# Boost.net
KiCad netlist of a schematic drawn in Altium Designer
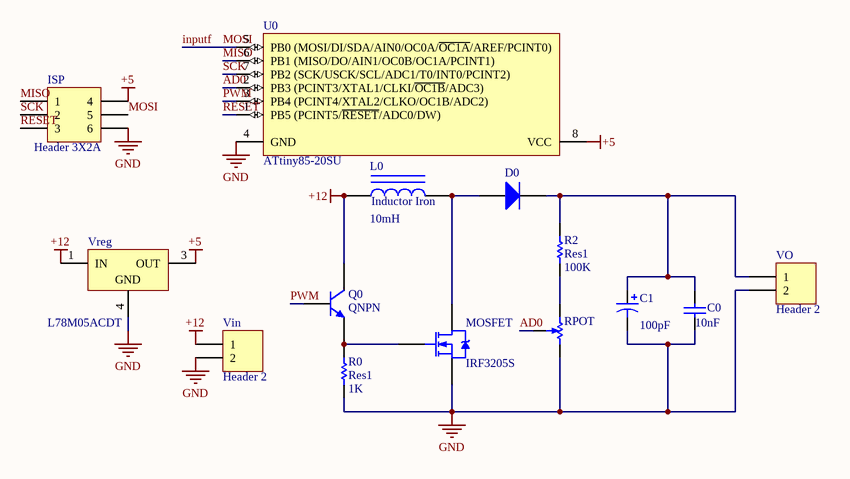
[diagram p0: Boost.SchDoc]

(export (version "E")
  (design (tool "Eeschema 10.0.6"))
  (components
    (comp (ref "C0")
      (value "10nF")
      (footprint "RB7.6-15")
      (description "Capacitor")
      (fields (field (name "Comment") "Cap") (field (name "PUBLISHER") "Altium Limited"))
      (libsource (lib "Miscellaneous Devices") (part "Cap"))
    )
    (comp (ref "C1")
      (value "100pF")
      (footprint "RAD-0.2")
      (description "Polarized Capacitor (Radial)")
      (fields (field (name "Comment") "Cap Pol1") (field (name "PUBLISHER") "Altium Limited"))
      (libsource (lib "Miscellaneous Devices") (part "Cap Pol1"))
    )
    (comp (ref "D0")
      (value "Diode BAS16")
      (footprint "SOT-23_L")
      (description "Silicon Switching Diode for High-Speed Switching")
      (fields (field (name "PUBLISHER") "Altium Limited"))
      (libsource (lib "Miscellaneous Devices") (part "Diode BAS16"))
    )
    (comp (ref "ISP")
      (value "Header 3X2A")
      (footprint "HDR2X3_CEN")
      (description "Header, 3-Pin, Dual row")
      (fields (field (name "PUBLISHER") "Altium Limited"))
      (libsource (lib "Miscellaneous Connectors") (part "Header 3X2A"))
    )
    (comp (ref "L0")
      (value "Inductor Iron")
      (footprint "AXIAL-0.9")
      (description "Magnetic-Core Inductor")
      (fields (field (name "ALTIUM_VALUE") "10mH") (field (name "PUBLISHER") "Altium Limited"))
      (libsource (lib "Miscellaneous Devices") (part "Inductor Iron"))
    )
    (comp (ref "MOSFET")
      (value "IRF3205S")
      (footprint "D2PAK_L")
      (description "HEXFET Power MOSFET")
      (fields (field (name "PUBLISHER") "Altium Limited"))
      (libsource (lib "IR Discrete MOSFET - Power") (part "IRF3205S"))
    )
    (comp (ref "Q0")
      (value "QNPN")
      (footprint "SOT-23B_L")
      (description "NPN Bipolar Transistor")
      (fields (field (name "PUBLISHER") "Altium Limited"))
      (libsource (lib "Miscellaneous Devices") (part "QNPN"))
    )
    (comp (ref "R0")
      (value "Res1")
      (footprint "j1-0603")
      (description "Resistor")
      (fields (field (name "ALTIUM_VALUE") "1K") (field (name "PUBLISHER") "Altium Limited"))
      (libsource (lib "Miscellaneous Devices") (part "Res1"))
    )
    (comp (ref "R2")
      (value "Res1")
      (footprint "j1-0603")
      (description "Resistor")
      (fields (field (name "ALTIUM_VALUE") "100K") (field (name "PUBLISHER") "Altium Limited"))
      (libsource (lib "Miscellaneous Devices") (part "Res1"))
    )
    (comp (ref "RPOT")
      (value "RPot SM")
      (footprint "POT4MM-2")
      (description "Square Trimming Potentiometer")
      (fields (field (name "PUBLISHER") "Altium Limited"))
      (libsource (lib "Miscellaneous Devices") (part "RPot SM"))
    )
    (comp (ref "U0")
      (value "ATtiny85-20SU")
      (footprint "8S2_L")
      (fields (field (name "PUBLISHER") "Altium Limited"))
      (libsource (lib "Atmel Microcontroller 8-Bit tinyAVR") (part "ATtiny85-20SU"))
    )
    (comp (ref "Vin")
      (value "Header 2")
      (footprint "HDR1X2")
      (description "Header, 2-Pin")
      (fields (field (name "PUBLISHER") "Altium Limited"))
      (libsource (lib "Miscellaneous Connectors") (part "Header 2"))
    )
    (comp (ref "VO")
      (value "Header 2")
      (footprint "HDR1X2")
      (description "Header, 2-Pin")
      (fields (field (name "PUBLISHER") "Altium Limited"))
      (libsource (lib "Miscellaneous Connectors") (part "Header 2"))
    )
    (comp (ref "Vreg")
      (value "L78M05ACDT")
      (footprint "TO-252")
      (description "Precision 500mA Regulator")
      (fields (field (name "PUBLISHER") "Altium Limited"))
      (libsource (lib "ST Power Mgt Voltage Regulator") (part "L78M05ACDT"))
    )
  )
  (nets
    (net (code "1") (name "+5") (class "Default")
      (node (ref "ISP") (pin "4") (pinfunction "4_4") (pintype "passive"))
      (node (ref "U0") (pin "8") (pinfunction "VCC_8") (pintype "power_in"))
      (node (ref "Vreg") (pin "3") (pinfunction "OUT_3") (pintype "power_in"))
    )
    (net (code "2") (name "+12") (class "Default")
      (node (ref "L0") (pin "1") (pinfunction "1_1") (pintype "passive"))
      (node (ref "Q0") (pin "1") (pinfunction "C_1") (pintype "passive"))
      (node (ref "Vin") (pin "1") (pinfunction "1_1") (pintype "passive"))
      (node (ref "Vreg") (pin "1") (pinfunction "IN_1") (pintype "power_in"))
    )
    (net (code "3") (name "/AD0") (class "Default")
      (node (ref "RPOT") (pin "W") (pinfunction "W_W") (pintype "passive"))
      (node (ref "U0") (pin "2") (pinfunction "PB3_(PCINT3/XTAL1/CLKI/~{OC1B}/ADC3)_2") (pintype "bidirectional"))
    )
    (net (code "4") (name "/MISO") (class "Default")
      (node (ref "ISP") (pin "1") (pinfunction "1_1") (pintype "passive"))
      (node (ref "U0") (pin "6") (pinfunction "PB1_(MISO/DO/AIN1/OC0B/OC1A/PCINT1)_6") (pintype "bidirectional"))
    )
    (net (code "5") (name "/MOSI") (class "Default")
      (node (ref "ISP") (pin "5") (pinfunction "5_5") (pintype "passive"))
      (node (ref "U0") (pin "5") (pinfunction "PB0_(MOSI/DI/SDA/AIN0/OC0A/~{OC1A}/AREF/PCINT0)_5") (pintype "bidirectional"))
    )
    (net (code "6") (name "/PWM") (class "Default")
      (node (ref "Q0") (pin "2") (pinfunction "B_2") (pintype "passive"))
      (node (ref "U0") (pin "3") (pinfunction "PB4_(PCINT4/XTAL2/CLKO/OC1B/ADC2)_3") (pintype "bidirectional"))
    )
    (net (code "7") (name "/RESET") (class "Default")
      (node (ref "ISP") (pin "3") (pinfunction "3_3") (pintype "passive"))
      (node (ref "U0") (pin "1") (pinfunction "PB5_(PCINT5/~{RESET}/ADC0/DW)_1") (pintype "bidirectional"))
    )
    (net (code "8") (name "/SCK") (class "Default")
      (node (ref "ISP") (pin "2") (pinfunction "2_2") (pintype "passive"))
      (node (ref "U0") (pin "7") (pinfunction "PB2_(SCK/USCK/SCL/ADC1/T0/INT0/PCINT2)_7") (pintype "bidirectional"))
    )
    (net (code "9") (name "GND") (class "Default")
      (node (ref "C0") (pin "1") (pinfunction "1_1") (pintype "passive"))
      (node (ref "C1") (pin "2") (pinfunction "2_2") (pintype "passive"))
      (node (ref "ISP") (pin "6") (pinfunction "6_6") (pintype "passive"))
      (node (ref "MOSFET") (pin "3") (pinfunction "S_3") (pintype "passive"))
      (node (ref "R0") (pin "1") (pinfunction "1_1") (pintype "passive"))
      (node (ref "RPOT") (pin "CW") (pinfunction "+_CW") (pintype "passive"))
      (node (ref "U0") (pin "4") (pinfunction "GND_4") (pintype "power_in"))
      (node (ref "VO") (pin "2") (pinfunction "2_2") (pintype "passive"))
      (node (ref "Vin") (pin "2") (pinfunction "2_2") (pintype "passive"))
      (node (ref "Vreg") (pin "4") (pinfunction "GND_4") (pintype "power_in"))
    )
    (net (code "10") (name "Net-(D0-A)") (class "Default")
      (node (ref "D0") (pin "1") (pinfunction "A_1") (pintype "passive"))
      (node (ref "L0") (pin "2") (pinfunction "2_2") (pintype "passive"))
      (node (ref "MOSFET") (pin "2") (pinfunction "D_2") (pintype "passive"))
    )
    (net (code "11") (name "Net-(D0-K)") (class "Default")
      (node (ref "C0") (pin "2") (pinfunction "2_2") (pintype "passive"))
      (node (ref "C1") (pin "1") (pinfunction "1_1") (pintype "passive"))
      (node (ref "D0") (pin "3") (pinfunction "K_3") (pintype "passive"))
      (node (ref "R2") (pin "2") (pinfunction "2_2") (pintype "passive"))
      (node (ref "VO") (pin "1") (pinfunction "1_1") (pintype "passive"))
    )
    (net (code "12") (name "Net-(MOSFET-G)") (class "Default")
      (node (ref "MOSFET") (pin "1") (pinfunction "G_1") (pintype "passive"))
      (node (ref "Q0") (pin "3") (pinfunction "E_3") (pintype "passive"))
      (node (ref "R0") (pin "2") (pinfunction "2_2") (pintype "passive"))
    )
    (net (code "13") (name "Net-(RPOT--)") (class "Default")
      (node (ref "R2") (pin "1") (pinfunction "1_1") (pintype "passive"))
      (node (ref "RPOT") (pin "CCW") (pinfunction "-_CCW") (pintype "passive"))
    )
  )
)
